# Sheet1.net
KiCad netlist of a schematic drawn in Altium Designer
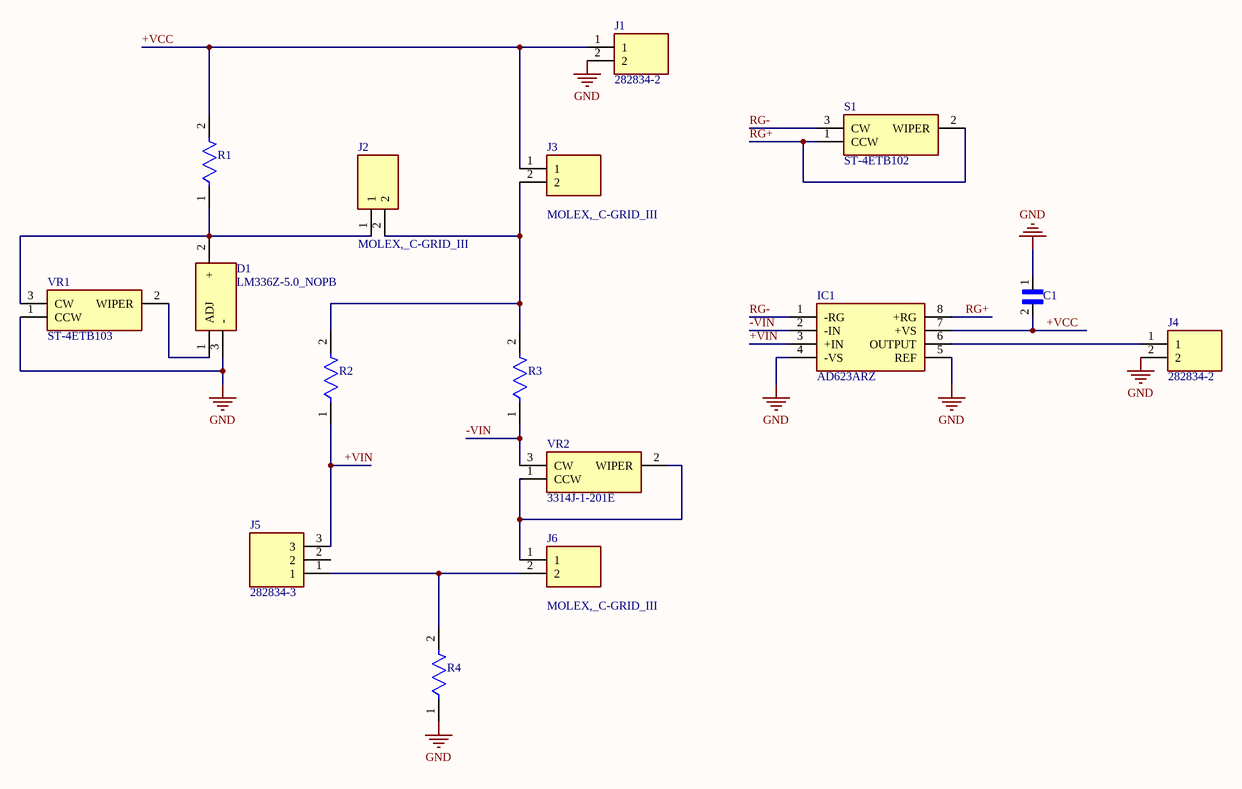
[diagram p0: Sheet1.SchDoc]

(export (version "E")
  (design (tool "Eeschema 10.0.6"))
  (components
    (comp (ref "C1")
      (value "Ceramic_Capacitor")
      (footprint "0603")
      (description "0.1 µF ±10% 50V Capacitores cerámicos X7R 0603 (1608 métrico)")
      (fields
        (field (name "MANUFACTURER") "Samsung")
        (field (name "MANUFACTURER PART NUMBER") "CL10B104KB8NNNC")
      )
      (libsource (lib "SchLib") (part "Ceramic_Capacitor"))
    )
    (comp (ref "D1")
      (value "LM336Z-5.0_NOPB")
      (footprint "PcbLib:LM336Z50NOPB")
      (description "Diode")
      (fields
        (field (name "MANUFACTURER") "Texas Instruments")
        (field (name "MANUFACTURER PART NUMBER") "LM336Z-5.0/NOPB")
      )
      (libsource (lib "*") (part "LM336Z-5.0_NOPB"))
    )
    (comp (ref "IC1")
      (value "AD623ARZ")
      (footprint "PcbLib:SOIC127P600X175-8N")
      (description "Integrated Circuit")
      (fields
        (field (name "MANUFACTURER") "Analog Devices")
        (field (name "MOUSER PART NUMBER") "584-AD623ARZ")
      )
      (libsource (lib "*") (part "AD623ARZ"))
    )
    (comp (ref "J1")
      (value "282834-2")
      (footprint "PcbLib:282834-2_1")
      (description "Connector")
      (fields
        (field (name "MANUFACTURER") "TE Connectivity")
        (field (name "MOUSER PART NUMBER") "571-282834-2")
      )
      (libsource (lib "*") (part "282834-2"))
    )
    (comp (ref "J2")
      (value "MOLEX,_C-GRID_III")
      (footprint "HDRV8W65P0X254_1X8_2010X249X945P")
      (description "Connector")
      (libsource (lib "") (part "MOLEX,_C-GRID_III,_90120,_8_WAY,_1_ROW,_STRAIGHT_PIN_HEADER_1"))
    )
    (comp (ref "J3")
      (value "MOLEX,_C-GRID_III")
      (footprint "HDRV8W65P0X254_1X8_2010X249X945P")
      (description "Connector")
      (libsource (lib "SchLib") (part "MOLEX,_C-GRID_III,_90120,_8_WAY,_1_ROW,_STRAIGHT_PIN_HEADER"))
    )
    (comp (ref "J4")
      (value "282834-2")
      (footprint "PcbLib:282834-2_1")
      (description "Connector")
      (fields
        (field (name "MANUFACTURER") "TE Connectivity")
        (field (name "MOUSER PART NUMBER") "571-282834-2")
      )
      (libsource (lib "*") (part "282834-2"))
    )
    (comp (ref "J5")
      (value "282834-3")
      (footprint "PcbLib:2828343")
      (description "Connector")
      (fields
        (field (name "MANUFACTURER") "TE Connectivity")
        (field (name "MOUSER PART NUMBER") "571-2828343")
      )
      (libsource (lib "*") (part "282834-3"))
    )
    (comp (ref "J6")
      (value "MOLEX,_C-GRID_III")
      (footprint "HDRV8W65P0X254_1X8_2010X249X945P")
      (description "Connector")
      (libsource (lib "SchLib") (part "MOLEX,_C-GRID_III,_90120,_8_WAY,_1_ROW,_STRAIGHT_PIN_HEADER"))
    )
    (comp (ref "R1")
      (value "Resistor")
      (footprint "0603")
      (fields
        (field (name "MANUFACTURER") "Yageo")
        (field (name "MANUFACTURER PART NUMBER") "RC0603FR-071K2L")
      )
      (libsource (lib "SchLib") (part "Resistor"))
    )
    (comp (ref "R2")
      (value "Resistor")
      (footprint "0603")
      (fields
        (field (name "MANUFACTURER") "Yageo")
        (field (name "MANUFACTURER PART NUMBER") "RC0603FR-074K7L")
      )
      (libsource (lib "SchLib") (part "Resistor"))
    )
    (comp (ref "R3")
      (value "Resistor")
      (footprint "0603")
      (fields
        (field (name "MANUFACTURER") "Yageo")
        (field (name "MANUFACTURER PART NUMBER") "RC0603FR-074K7L")
      )
      (libsource (lib "SchLib") (part "Resistor"))
    )
    (comp (ref "R4")
      (value "Resistor")
      (footprint "0603")
      (fields
        (field (name "MANUFACTURER") "Yageo")
        (field (name "MANUFACTURER PART NUMBER") "RC0603FR-071K2L")
      )
      (libsource (lib "SchLib") (part "Resistor"))
    )
    (comp (ref "S1")
      (value "ST-4ETB102")
      (footprint "PcbLib:ST4ETB102")
      (description "Switch")
      (fields
        (field (name "MANUFACTURER") "NIDEC COPAL")
        (field (name "MOUSER PART NUMBER") "229-ST-4ETB102")
      )
      (libsource (lib "*") (part "ST-4ETB102"))
    )
    (comp (ref "VR1")
      (value "ST-4ETB103")
      (footprint "PcbLib:ST4ETB103")
      (description "Variable Resistor")
      (fields
        (field (name "MANUFACTURER") "NIDEC COPAL")
        (field (name "MOUSER PART NUMBER") "229-ST-4ETB103")
      )
      (libsource (lib "*") (part "ST-4ETB103"))
    )
    (comp (ref "VR2")
      (value "3314J-1-201E")
      (footprint "PcbLib:3314J1201E")
      (description "Variable Resistor")
      (fields (field (name "MANUFACTURER") "Bourns") (field (name "MOUSER PART NUMBER") "652-3314J-1-201E"))
      (libsource (lib "*") (part "3314J-1-201E"))
    )
  )
  (nets
    (net (code "1") (name "/+VCC") (class "Default")
      (node (ref "C1") (pin "2") (pinfunction "2_2") (pintype "passive"))
      (node (ref "IC1") (pin "7") (pinfunction "+VS_7") (pintype "passive"))
      (node (ref "J1") (pin "1") (pinfunction "1_1") (pintype "passive"))
      (node (ref "J3") (pin "1") (pinfunction "1_1") (pintype "passive"))
      (node (ref "R1") (pin "2") (pinfunction "2_2") (pintype "passive"))
    )
    (net (code "2") (name "/+VIN") (class "Default")
      (node (ref "IC1") (pin "3") (pinfunction "+IN_3") (pintype "passive"))
      (node (ref "J5") (pin "3") (pinfunction "3_3") (pintype "passive"))
      (node (ref "R2") (pin "1") (pinfunction "1_1") (pintype "passive"))
    )
    (net (code "3") (name "/-VIN") (class "Default")
      (node (ref "IC1") (pin "2") (pinfunction "-IN_2") (pintype "passive"))
      (node (ref "R3") (pin "1") (pinfunction "1_1") (pintype "passive"))
      (node (ref "VR2") (pin "3") (pinfunction "CW_3") (pintype "passive"))
    )
    (net (code "4") (name "/RG+") (class "Default")
      (node (ref "IC1") (pin "8") (pinfunction "+RG_8") (pintype "passive"))
      (node (ref "S1") (pin "1") (pinfunction "CCW_1") (pintype "passive"))
      (node (ref "S1") (pin "2") (pinfunction "WIPER_2") (pintype "passive"))
    )
    (net (code "5") (name "/RG-") (class "Default")
      (node (ref "IC1") (pin "1") (pinfunction "-RG_1") (pintype "passive"))
      (node (ref "S1") (pin "3") (pinfunction "CW_3") (pintype "passive"))
    )
    (net (code "6") (name "GND") (class "Default")
      (node (ref "C1") (pin "1") (pinfunction "1_1") (pintype "passive"))
      (node (ref "D1") (pin "3") (pinfunction "-_3") (pintype "passive"))
      (node (ref "IC1") (pin "4") (pinfunction "-VS_4") (pintype "passive"))
      (node (ref "IC1") (pin "5") (pinfunction "REF_5") (pintype "passive"))
      (node (ref "J1") (pin "2") (pinfunction "2_2") (pintype "passive"))
      (node (ref "J4") (pin "2") (pinfunction "2_2") (pintype "passive"))
      (node (ref "R4") (pin "1") (pinfunction "1_1") (pintype "passive"))
      (node (ref "VR1") (pin "1") (pinfunction "CCW_1") (pintype "passive"))
    )
    (net (code "7") (name "Net-(D1-+)") (class "Default")
      (node (ref "D1") (pin "2") (pinfunction "+_2") (pintype "passive"))
      (node (ref "J2") (pin "1") (pinfunction "1_1") (pintype "passive"))
      (node (ref "R1") (pin "1") (pinfunction "1_1") (pintype "passive"))
      (node (ref "VR1") (pin "3") (pinfunction "CW_3") (pintype "passive"))
    )
    (net (code "8") (name "Net-(D1-ADJ)") (class "Default")
      (node (ref "D1") (pin "1") (pinfunction "ADJ_1") (pintype "passive"))
      (node (ref "VR1") (pin "2") (pinfunction "WIPER_2") (pintype "passive"))
    )
    (net (code "9") (name "Net-(IC1-OUTPUT)") (class "Default")
      (node (ref "IC1") (pin "6") (pinfunction "OUTPUT_6") (pintype "passive"))
      (node (ref "J4") (pin "1") (pinfunction "1_1") (pintype "passive"))
    )
    (net (code "10") (name "Net-(J2-Pad2)") (class "Default")
      (node (ref "J2") (pin "2") (pinfunction "2_2") (pintype "passive"))
      (node (ref "J3") (pin "2") (pinfunction "2_2") (pintype "passive"))
      (node (ref "R2") (pin "2") (pinfunction "2_2") (pintype "passive"))
      (node (ref "R3") (pin "2") (pinfunction "2_2") (pintype "passive"))
    )
    (net (code "11") (name "Net-(J5-Pad1)") (class "Default")
      (node (ref "J5") (pin "1") (pinfunction "1_1") (pintype "passive"))
      (node (ref "J6") (pin "2") (pinfunction "2_2") (pintype "passive"))
      (node (ref "R4") (pin "2") (pinfunction "2_2") (pintype "passive"))
    )
    (net (code "12") (name "Net-(VR2-CCW)") (class "Default")
      (node (ref "J6") (pin "1") (pinfunction "1_1") (pintype "passive"))
      (node (ref "VR2") (pin "1") (pinfunction "CCW_1") (pintype "passive"))
      (node (ref "VR2") (pin "2") (pinfunction "WIPER_2") (pintype "passive"))
    )
    (net (code "13") (name "unconnected-(J5-Pad2)") (class "Default")
      (node (ref "J5") (pin "2") (pinfunction "2_2") (pintype "passive"))
    )
  )
)
